# Car.net
KiCad netlist of a schematic drawn in EAGLE
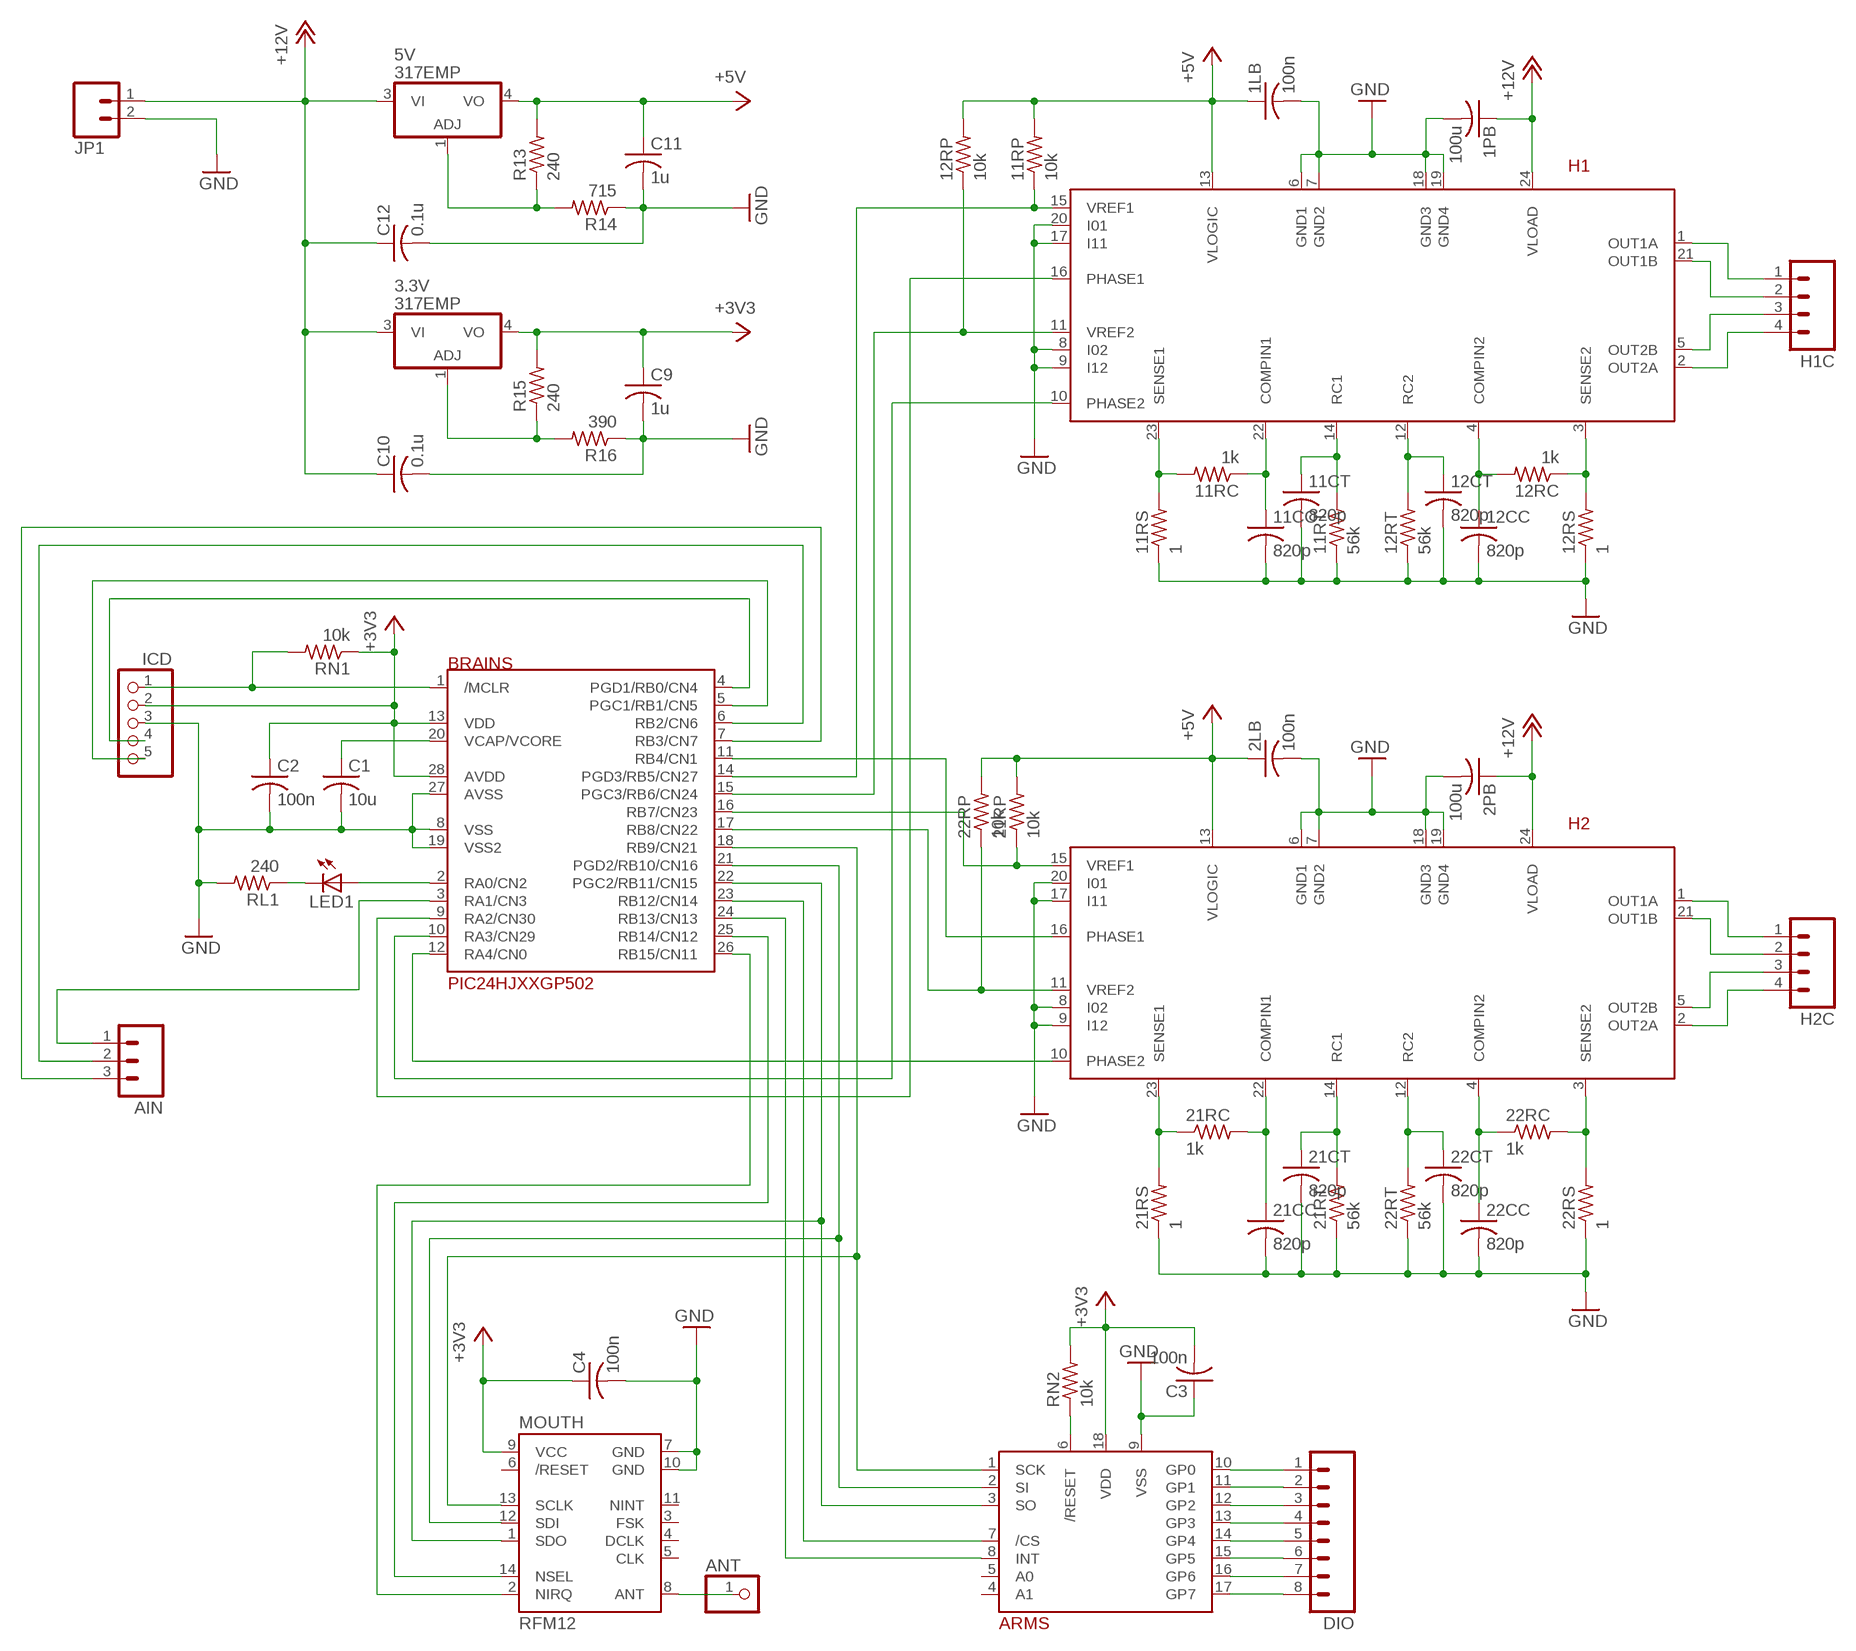
[diagram p0: schematic, sheet 1]

(export (version "E")
  (design (tool "Eeschema 10.0.6"))
  (components
    (comp (ref "1LB")
      (value "100n")
      (footprint "eagle-import:C0805")
      (libsource (lib "eagle-import") (part "C-USC0805"))
    )
    (comp (ref "1PB")
      (value "100u")
      (footprint "eagle-import:C0805")
      (libsource (lib "eagle-import") (part "C-USC0805"))
    )
    (comp (ref "2LB")
      (value "100n")
      (footprint "eagle-import:C0805")
      (libsource (lib "eagle-import") (part "C-USC0805"))
    )
    (comp (ref "2PB")
      (value "100u")
      (footprint "eagle-import:C0805")
      (libsource (lib "eagle-import") (part "C-USC0805"))
    )
    (comp (ref "3.3V")
      (value "317EMP")
      (footprint "eagle-import:SOT223")
      (libsource (lib "eagle-import") (part "317EMP"))
    )
    (comp (ref "5V")
      (value "317EMP")
      (footprint "eagle-import:SOT223")
      (libsource (lib "eagle-import") (part "317EMP"))
    )
    (comp (ref "11CC")
      (value "820p")
      (footprint "eagle-import:C0805")
      (libsource (lib "eagle-import") (part "C-USC0805"))
    )
    (comp (ref "11CT")
      (value "820p")
      (footprint "eagle-import:C0805")
      (libsource (lib "eagle-import") (part "C-USC0805"))
    )
    (comp (ref "11RC")
      (value "1k")
      (footprint "eagle-import:R0805")
      (libsource (lib "eagle-import") (part "R-US_R0805"))
    )
    (comp (ref "11RP")
      (value "10k")
      (footprint "eagle-import:R0805")
      (libsource (lib "eagle-import") (part "R-US_R0805"))
    )
    (comp (ref "11RS")
      (value "1")
      (footprint "eagle-import:R2512")
      (libsource (lib "eagle-import") (part "resistor_R-US_R2512"))
    )
    (comp (ref "11RT")
      (value "56k")
      (footprint "eagle-import:R0805")
      (libsource (lib "eagle-import") (part "R-US_R0805"))
    )
    (comp (ref "12CC")
      (value "820p")
      (footprint "eagle-import:C0805")
      (libsource (lib "eagle-import") (part "C-USC0805"))
    )
    (comp (ref "12CT")
      (value "820p")
      (footprint "eagle-import:C0805")
      (libsource (lib "eagle-import") (part "C-USC0805"))
    )
    (comp (ref "12RC")
      (value "1k")
      (footprint "eagle-import:R0805")
      (libsource (lib "eagle-import") (part "R-US_R0805"))
    )
    (comp (ref "12RP")
      (value "10k")
      (footprint "eagle-import:R0805")
      (libsource (lib "eagle-import") (part "R-US_R0805"))
    )
    (comp (ref "12RS")
      (value "1")
      (footprint "eagle-import:R2512")
      (libsource (lib "eagle-import") (part "resistor_R-US_R2512"))
    )
    (comp (ref "12RT")
      (value "56k")
      (footprint "eagle-import:R0805")
      (libsource (lib "eagle-import") (part "R-US_R0805"))
    )
    (comp (ref "21CC")
      (value "820p")
      (footprint "eagle-import:C0805")
      (libsource (lib "eagle-import") (part "C-USC0805"))
    )
    (comp (ref "21CT")
      (value "820p")
      (footprint "eagle-import:C0805")
      (libsource (lib "eagle-import") (part "C-USC0805"))
    )
    (comp (ref "21RC")
      (value "1k")
      (footprint "eagle-import:R0805")
      (libsource (lib "eagle-import") (part "R-US_R0805"))
    )
    (comp (ref "21RP")
      (value "10k")
      (footprint "eagle-import:R0805")
      (libsource (lib "eagle-import") (part "R-US_R0805"))
    )
    (comp (ref "21RS")
      (value "1")
      (footprint "eagle-import:R2512")
      (libsource (lib "eagle-import") (part "resistor_R-US_R2512"))
    )
    (comp (ref "21RT")
      (value "56k")
      (footprint "eagle-import:R0805")
      (libsource (lib "eagle-import") (part "R-US_R0805"))
    )
    (comp (ref "22CC")
      (value "820p")
      (footprint "eagle-import:C0805")
      (libsource (lib "eagle-import") (part "C-USC0805"))
    )
    (comp (ref "22CT")
      (value "820p")
      (footprint "eagle-import:C0805")
      (libsource (lib "eagle-import") (part "C-USC0805"))
    )
    (comp (ref "22RC")
      (value "1k")
      (footprint "eagle-import:R0805")
      (libsource (lib "eagle-import") (part "R-US_R0805"))
    )
    (comp (ref "22RP")
      (value "10k")
      (footprint "eagle-import:R0805")
      (libsource (lib "eagle-import") (part "R-US_R0805"))
    )
    (comp (ref "22RS")
      (value "1")
      (footprint "eagle-import:R2512")
      (libsource (lib "eagle-import") (part "resistor_R-US_R2512"))
    )
    (comp (ref "22RT")
      (value "56k")
      (footprint "eagle-import:R0805")
      (libsource (lib "eagle-import") (part "R-US_R0805"))
    )
    (comp (ref "AIN")
      (value "M03POLAR")
      (footprint "eagle-import:MOLEX-1X3")
      (libsource (lib "eagle-import") (part "M03POLAR"))
    )
    (comp (ref "ANT")
      (value "PINHD-1X1")
      (footprint "eagle-import:1X01")
      (libsource (lib "eagle-import") (part "PINHD-1X1"))
    )
    (comp (ref "ARMS")
      (value "MCP23S08")
      (footprint "eagle-import:SO-18W")
      (libsource (lib "eagle-import") (part "MCP23S08"))
    )
    (comp (ref "BRAINS")
      (value "PIC24HJXXGP502")
      (footprint "eagle-import:SO28W")
      (libsource (lib "eagle-import") (part "PIC24HJXXGP502"))
    )
    (comp (ref "C1")
      (value "10u")
      (footprint "eagle-import:C0805")
      (libsource (lib "eagle-import") (part "C-USC0805"))
    )
    (comp (ref "C2")
      (value "100n")
      (footprint "eagle-import:C0805")
      (libsource (lib "eagle-import") (part "C-USC0805"))
    )
    (comp (ref "C3")
      (value "100n")
      (footprint "eagle-import:C0805")
      (libsource (lib "eagle-import") (part "C-USC0805"))
    )
    (comp (ref "C4")
      (value "100n")
      (footprint "eagle-import:C0805")
      (libsource (lib "eagle-import") (part "C-USC0805"))
    )
    (comp (ref "C9")
      (value "1u")
      (footprint "eagle-import:C0805")
      (libsource (lib "eagle-import") (part "C-USC0805"))
    )
    (comp (ref "C10")
      (value "0.1u")
      (footprint "eagle-import:C0805")
      (libsource (lib "eagle-import") (part "C-USC0805"))
    )
    (comp (ref "C11")
      (value "1u")
      (footprint "eagle-import:C0805")
      (libsource (lib "eagle-import") (part "C-USC0805"))
    )
    (comp (ref "C12")
      (value "0.1u")
      (footprint "eagle-import:C0805")
      (libsource (lib "eagle-import") (part "C-USC0805"))
    )
    (comp (ref "DIO")
      (value "M081X08")
      (footprint "eagle-import:1X08")
      (libsource (lib "eagle-import") (part "M081X08"))
    )
    (comp (ref "H1")
      (value "MTS62C19A")
      (footprint "eagle-import:SOP24L")
      (libsource (lib "eagle-import") (part "MTS62C19A"))
    )
    (comp (ref "H1C")
      (value "M04POLAR")
      (footprint "eagle-import:MOLEX-1X4")
      (libsource (lib "eagle-import") (part "M04POLAR"))
    )
    (comp (ref "H2")
      (value "MTS62C19A")
      (footprint "eagle-import:SOP24L")
      (libsource (lib "eagle-import") (part "MTS62C19A"))
    )
    (comp (ref "H2C")
      (value "M04POLAR")
      (footprint "eagle-import:MOLEX-1X4")
      (libsource (lib "eagle-import") (part "M04POLAR"))
    )
    (comp (ref "ICD")
      (value "PINHD-1X5")
      (footprint "eagle-import:1X05")
      (libsource (lib "eagle-import") (part "PINHD-1X5"))
    )
    (comp (ref "JP1")
      (value "M02POLAR")
      (footprint "eagle-import:MOLEX-1X2")
      (libsource (lib "eagle-import") (part "M02POLAR"))
    )
    (comp (ref "LED1")
      (value "LEDCHIP-LED0805")
      (footprint "eagle-import:CHIP-LED0805")
      (libsource (lib "eagle-import") (part "LEDCHIP-LED0805"))
    )
    (comp (ref "MOUTH")
      (value "RFM12")
      (footprint "eagle-import:RFM12-XXX-S2")
      (libsource (lib "eagle-import") (part "RFM12"))
    )
    (comp (ref "R13")
      (value "240")
      (footprint "eagle-import:R0805")
      (libsource (lib "eagle-import") (part "R-US_R0805"))
    )
    (comp (ref "R14")
      (value "715")
      (footprint "eagle-import:R0805")
      (libsource (lib "eagle-import") (part "R-US_R0805"))
    )
    (comp (ref "R15")
      (value "240")
      (footprint "eagle-import:R0805")
      (libsource (lib "eagle-import") (part "R-US_R0805"))
    )
    (comp (ref "R16")
      (value "390")
      (footprint "eagle-import:R0805")
      (libsource (lib "eagle-import") (part "R-US_R0805"))
    )
    (comp (ref "RL1")
      (value "240")
      (footprint "eagle-import:R0805")
      (libsource (lib "eagle-import") (part "R-US_R0805"))
    )
    (comp (ref "RN1")
      (value "10k")
      (footprint "eagle-import:R0805")
      (libsource (lib "eagle-import") (part "R-US_R0805"))
    )
    (comp (ref "RN2")
      (value "10k")
      (footprint "eagle-import:R0805")
      (libsource (lib "eagle-import") (part "R-US_R0805"))
    )
  )
  (nets
    (net (code "1") (name "+3V3") (class "Default")
      (node (ref "3.3V") (pin "4") (pinfunction "VO_4") (pintype "passive"))
      (node (ref "ARMS") (pin "18") (pinfunction "VDD_18") (pintype "bidirectional"))
      (node (ref "BRAINS") (pin "13") (pinfunction "VDD_13") (pintype "bidirectional"))
      (node (ref "BRAINS") (pin "28") (pinfunction "AVDD_28") (pintype "bidirectional"))
      (node (ref "C2") (pin "1") (pinfunction "1_1") (pintype "passive"))
      (node (ref "C3") (pin "2") (pinfunction "2_2") (pintype "passive"))
      (node (ref "C4") (pin "1") (pinfunction "1_1") (pintype "passive"))
      (node (ref "C9") (pin "1") (pinfunction "1_1") (pintype "passive"))
      (node (ref "ICD") (pin "2") (pinfunction "2_2") (pintype "passive"))
      (node (ref "MOUTH") (pin "9") (pinfunction "VCC_9") (pintype "bidirectional"))
      (node (ref "R15") (pin "2") (pinfunction "2_2") (pintype "passive"))
      (node (ref "RN1") (pin "1") (pinfunction "1_1") (pintype "passive"))
      (node (ref "RN2") (pin "2") (pinfunction "2_2") (pintype "passive"))
    )
    (net (code "2") (name "+5V") (class "Default")
      (node (ref "11RP") (pin "2") (pinfunction "2_2") (pintype "passive"))
      (node (ref "12RP") (pin "2") (pinfunction "2_2") (pintype "passive"))
      (node (ref "1LB") (pin "1") (pinfunction "1_1") (pintype "passive"))
      (node (ref "21RP") (pin "2") (pinfunction "2_2") (pintype "passive"))
      (node (ref "22RP") (pin "2") (pinfunction "2_2") (pintype "passive"))
      (node (ref "2LB") (pin "1") (pinfunction "1_1") (pintype "passive"))
      (node (ref "5V") (pin "4") (pinfunction "VO_4") (pintype "passive"))
      (node (ref "C11") (pin "1") (pinfunction "1_1") (pintype "passive"))
      (node (ref "H1") (pin "13") (pinfunction "VLOGIC_13") (pintype "bidirectional"))
      (node (ref "H2") (pin "13") (pinfunction "VLOGIC_13") (pintype "bidirectional"))
      (node (ref "R13") (pin "2") (pinfunction "2_2") (pintype "passive"))
    )
    (net (code "3") (name "+12V") (class "Default")
      (node (ref "1PB") (pin "1") (pinfunction "1_1") (pintype "passive"))
      (node (ref "2PB") (pin "1") (pinfunction "1_1") (pintype "passive"))
      (node (ref "3.3V") (pin "3") (pinfunction "VI_3") (pintype "input"))
      (node (ref "5V") (pin "3") (pinfunction "VI_3") (pintype "input"))
      (node (ref "C10") (pin "1") (pinfunction "1_1") (pintype "passive"))
      (node (ref "C12") (pin "1") (pinfunction "1_1") (pintype "passive"))
      (node (ref "H1") (pin "24") (pinfunction "VLOAD_24") (pintype "bidirectional"))
      (node (ref "H2") (pin "24") (pinfunction "VLOAD_24") (pintype "bidirectional"))
      (node (ref "JP1") (pin "1") (pinfunction "1_1") (pintype "passive"))
    )
    (net (code "4") (name "GND") (class "Default")
      (node (ref "11CC") (pin "2") (pinfunction "2_2") (pintype "passive"))
      (node (ref "11CT") (pin "2") (pinfunction "2_2") (pintype "passive"))
      (node (ref "11RS") (pin "1") (pinfunction "1_1") (pintype "passive"))
      (node (ref "11RT") (pin "1") (pinfunction "1_1") (pintype "passive"))
      (node (ref "12CC") (pin "2") (pinfunction "2_2") (pintype "passive"))
      (node (ref "12CT") (pin "2") (pinfunction "2_2") (pintype "passive"))
      (node (ref "12RS") (pin "1") (pinfunction "1_1") (pintype "passive"))
      (node (ref "12RT") (pin "1") (pinfunction "1_1") (pintype "passive"))
      (node (ref "1LB") (pin "2") (pinfunction "2_2") (pintype "passive"))
      (node (ref "1PB") (pin "2") (pinfunction "2_2") (pintype "passive"))
      (node (ref "21CC") (pin "2") (pinfunction "2_2") (pintype "passive"))
      (node (ref "21CT") (pin "2") (pinfunction "2_2") (pintype "passive"))
      (node (ref "21RS") (pin "1") (pinfunction "1_1") (pintype "passive"))
      (node (ref "21RT") (pin "1") (pinfunction "1_1") (pintype "passive"))
      (node (ref "22CC") (pin "2") (pinfunction "2_2") (pintype "passive"))
      (node (ref "22CT") (pin "2") (pinfunction "2_2") (pintype "passive"))
      (node (ref "22RS") (pin "1") (pinfunction "1_1") (pintype "passive"))
      (node (ref "22RT") (pin "1") (pinfunction "1_1") (pintype "passive"))
      (node (ref "2LB") (pin "2") (pinfunction "2_2") (pintype "passive"))
      (node (ref "2PB") (pin "2") (pinfunction "2_2") (pintype "passive"))
      (node (ref "ARMS") (pin "9") (pinfunction "VSS_9") (pintype "bidirectional"))
      (node (ref "BRAINS") (pin "19") (pinfunction "VSS2_19") (pintype "bidirectional"))
      (node (ref "BRAINS") (pin "27") (pinfunction "AVSS_27") (pintype "bidirectional"))
      (node (ref "BRAINS") (pin "8") (pinfunction "VSS_8") (pintype "bidirectional"))
      (node (ref "C1") (pin "2") (pinfunction "2_2") (pintype "passive"))
      (node (ref "C10") (pin "2") (pinfunction "2_2") (pintype "passive"))
      (node (ref "C11") (pin "2") (pinfunction "2_2") (pintype "passive"))
      (node (ref "C12") (pin "2") (pinfunction "2_2") (pintype "passive"))
      (node (ref "C2") (pin "2") (pinfunction "2_2") (pintype "passive"))
      (node (ref "C3") (pin "1") (pinfunction "1_1") (pintype "passive"))
      (node (ref "C4") (pin "2") (pinfunction "2_2") (pintype "passive"))
      (node (ref "C9") (pin "2") (pinfunction "2_2") (pintype "passive"))
      (node (ref "H1") (pin "17") (pinfunction "I11_17") (pintype "bidirectional"))
      (node (ref "H1") (pin "18") (pinfunction "GND3_18") (pintype "bidirectional"))
      (node (ref "H1") (pin "19") (pinfunction "GND4_19") (pintype "bidirectional"))
      (node (ref "H1") (pin "20") (pinfunction "I01_20") (pintype "bidirectional"))
      (node (ref "H1") (pin "6") (pinfunction "GND1_6") (pintype "bidirectional"))
      (node (ref "H1") (pin "7") (pinfunction "GND2_7") (pintype "bidirectional"))
      (node (ref "H1") (pin "8") (pinfunction "I02_8") (pintype "bidirectional"))
      (node (ref "H1") (pin "9") (pinfunction "I12_9") (pintype "bidirectional"))
      (node (ref "H2") (pin "17") (pinfunction "I11_17") (pintype "bidirectional"))
      (node (ref "H2") (pin "18") (pinfunction "GND3_18") (pintype "bidirectional"))
      (node (ref "H2") (pin "19") (pinfunction "GND4_19") (pintype "bidirectional"))
      (node (ref "H2") (pin "20") (pinfunction "I01_20") (pintype "bidirectional"))
      (node (ref "H2") (pin "6") (pinfunction "GND1_6") (pintype "bidirectional"))
      (node (ref "H2") (pin "7") (pinfunction "GND2_7") (pintype "bidirectional"))
      (node (ref "H2") (pin "8") (pinfunction "I02_8") (pintype "bidirectional"))
      (node (ref "H2") (pin "9") (pinfunction "I12_9") (pintype "bidirectional"))
      (node (ref "ICD") (pin "3") (pinfunction "3_3") (pintype "passive"))
      (node (ref "JP1") (pin "2") (pinfunction "2_2") (pintype "passive"))
      (node (ref "MOUTH") (pin "10") (pinfunction "GND_10") (pintype "bidirectional"))
      (node (ref "MOUTH") (pin "7") (pinfunction "GND_7") (pintype "bidirectional"))
      (node (ref "R14") (pin "1") (pinfunction "1_1") (pintype "passive"))
      (node (ref "R16") (pin "1") (pinfunction "1_1") (pintype "passive"))
      (node (ref "RL1") (pin "2") (pinfunction "2_2") (pintype "passive"))
    )
    (net (code "5") (name "Net-(3.3V-ADJ)") (class "Default")
      (node (ref "3.3V") (pin "1") (pinfunction "ADJ_1") (pintype "input"))
      (node (ref "R15") (pin "1") (pinfunction "1_1") (pintype "passive"))
      (node (ref "R16") (pin "2") (pinfunction "2_2") (pintype "passive"))
    )
    (net (code "6") (name "Net-(5V-ADJ)") (class "Default")
      (node (ref "5V") (pin "1") (pinfunction "ADJ_1") (pintype "input"))
      (node (ref "R13") (pin "1") (pinfunction "1_1") (pintype "passive"))
      (node (ref "R14") (pin "2") (pinfunction "2_2") (pintype "passive"))
    )
    (net (code "7") (name "Net-(ARMS-GP0)") (class "Default")
      (node (ref "ARMS") (pin "10") (pinfunction "GP0_10") (pintype "bidirectional"))
      (node (ref "DIO") (pin "1") (pinfunction "1_1") (pintype "passive"))
    )
    (net (code "8") (name "Net-(ARMS-GP1)") (class "Default")
      (node (ref "ARMS") (pin "11") (pinfunction "GP1_11") (pintype "bidirectional"))
      (node (ref "DIO") (pin "2") (pinfunction "2_2") (pintype "passive"))
    )
    (net (code "9") (name "Net-(ARMS-GP2)") (class "Default")
      (node (ref "ARMS") (pin "12") (pinfunction "GP2_12") (pintype "bidirectional"))
      (node (ref "DIO") (pin "3") (pinfunction "3_3") (pintype "passive"))
    )
    (net (code "10") (name "Net-(ARMS-GP3)") (class "Default")
      (node (ref "ARMS") (pin "13") (pinfunction "GP3_13") (pintype "bidirectional"))
      (node (ref "DIO") (pin "4") (pinfunction "4_4") (pintype "passive"))
    )
    (net (code "11") (name "Net-(ARMS-GP4)") (class "Default")
      (node (ref "ARMS") (pin "14") (pinfunction "GP4_14") (pintype "bidirectional"))
      (node (ref "DIO") (pin "5") (pinfunction "5_5") (pintype "passive"))
    )
    (net (code "12") (name "Net-(ARMS-GP5)") (class "Default")
      (node (ref "ARMS") (pin "15") (pinfunction "GP5_15") (pintype "bidirectional"))
      (node (ref "DIO") (pin "6") (pinfunction "6_6") (pintype "passive"))
    )
    (net (code "13") (name "Net-(ARMS-GP6)") (class "Default")
      (node (ref "ARMS") (pin "16") (pinfunction "GP6_16") (pintype "bidirectional"))
      (node (ref "DIO") (pin "7") (pinfunction "7_7") (pintype "passive"))
    )
    (net (code "14") (name "Net-(ARMS-GP7)") (class "Default")
      (node (ref "ARMS") (pin "17") (pinfunction "GP7_17") (pintype "bidirectional"))
      (node (ref "DIO") (pin "8") (pinfunction "8_8") (pintype "passive"))
    )
    (net (code "15") (name "Net-(ARMS-INT)") (class "Default")
      (node (ref "ARMS") (pin "8") (pinfunction "INT_8") (pintype "bidirectional"))
      (node (ref "BRAINS") (pin "24") (pinfunction "RB13/CN13_24") (pintype "bidirectional"))
    )
    (net (code "16") (name "Net-(ARMS-SCK)") (class "Default")
      (node (ref "ARMS") (pin "1") (pinfunction "SCK_1") (pintype "bidirectional"))
      (node (ref "BRAINS") (pin "18") (pinfunction "RB9/CN21_18") (pintype "bidirectional"))
      (node (ref "MOUTH") (pin "13") (pinfunction "SCLK_13") (pintype "input"))
    )
    (net (code "17") (name "Net-(ARMS-SI)") (class "Default")
      (node (ref "ARMS") (pin "2") (pinfunction "SI_2") (pintype "bidirectional"))
      (node (ref "BRAINS") (pin "21") (pinfunction "PGD2/RB10/CN16_21") (pintype "bidirectional"))
      (node (ref "MOUTH") (pin "12") (pinfunction "SDI_12") (pintype "input"))
    )
    (net (code "18") (name "Net-(ARMS-SO)") (class "Default")
      (node (ref "ARMS") (pin "3") (pinfunction "SO_3") (pintype "bidirectional"))
      (node (ref "BRAINS") (pin "22") (pinfunction "PGC2/RB11/CN15_22") (pintype "bidirectional"))
      (node (ref "MOUTH") (pin "1") (pinfunction "SDO_1") (pintype "output"))
    )
    (net (code "19") (name "Net-(ARMS-{slash}CS)") (class "Default")
      (node (ref "ARMS") (pin "7") (pinfunction "/CS_7") (pintype "bidirectional"))
      (node (ref "BRAINS") (pin "23") (pinfunction "RB12/CN14_23") (pintype "bidirectional"))
    )
    (net (code "20") (name "Net-(ARMS-{slash}RESET)") (class "Default")
      (node (ref "ARMS") (pin "6") (pinfunction "/RESET_6") (pintype "bidirectional"))
      (node (ref "RN2") (pin "1") (pinfunction "1_1") (pintype "passive"))
    )
    (net (code "21") (name "Net-(BRAINS-PGC1{slash}RB1{slash}CN5)") (class "Default")
      (node (ref "BRAINS") (pin "5") (pinfunction "PGC1/RB1/CN5_5") (pintype "bidirectional"))
      (node (ref "ICD") (pin "5") (pinfunction "5_5") (pintype "passive"))
    )
    (net (code "22") (name "Net-(BRAINS-PGC3{slash}RB6{slash}CN24)") (class "Default")
      (node (ref "12RP") (pin "1") (pinfunction "1_1") (pintype "passive"))
      (node (ref "BRAINS") (pin "15") (pinfunction "PGC3/RB6/CN24_15") (pintype "bidirectional"))
      (node (ref "H1") (pin "11") (pinfunction "VREF2_11") (pintype "bidirectional"))
    )
    (net (code "23") (name "Net-(BRAINS-PGD1{slash}RB0{slash}CN4)") (class "Default")
      (node (ref "BRAINS") (pin "4") (pinfunction "PGD1/RB0/CN4_4") (pintype "bidirectional"))
      (node (ref "ICD") (pin "4") (pinfunction "4_4") (pintype "passive"))
    )
    (net (code "24") (name "Net-(BRAINS-PGD3{slash}RB5{slash}CN27)") (class "Default")
      (node (ref "11RP") (pin "1") (pinfunction "1_1") (pintype "passive"))
      (node (ref "BRAINS") (pin "14") (pinfunction "PGD3/RB5/CN27_14") (pintype "bidirectional"))
      (node (ref "H1") (pin "15") (pinfunction "VREF1_15") (pintype "bidirectional"))
    )
    (net (code "25") (name "Net-(BRAINS-RA0{slash}CN2)") (class "Default")
      (node (ref "BRAINS") (pin "2") (pinfunction "RA0/CN2_2") (pintype "bidirectional"))
      (node (ref "LED1") (pin "A") (pinfunction "A_A") (pintype "passive"))
    )
    (net (code "26") (name "Net-(BRAINS-RA1{slash}CN3)") (class "Default")
      (node (ref "AIN") (pin "1") (pinfunction "1_1") (pintype "passive"))
      (node (ref "BRAINS") (pin "3") (pinfunction "RA1/CN3_3") (pintype "bidirectional"))
    )
    (net (code "27") (name "Net-(BRAINS-RA2{slash}CN30)") (class "Default")
      (node (ref "BRAINS") (pin "9") (pinfunction "RA2/CN30_9") (pintype "bidirectional"))
      (node (ref "H1") (pin "16") (pinfunction "PHASE1_16") (pintype "bidirectional"))
    )
    (net (code "28") (name "Net-(BRAINS-RA3{slash}CN29)") (class "Default")
      (node (ref "BRAINS") (pin "10") (pinfunction "RA3/CN29_10") (pintype "bidirectional"))
      (node (ref "H1") (pin "10") (pinfunction "PHASE2_10") (pintype "bidirectional"))
    )
    (net (code "29") (name "Net-(BRAINS-RA4{slash}CN0)") (class "Default")
      (node (ref "BRAINS") (pin "12") (pinfunction "RA4/CN0_12") (pintype "bidirectional"))
      (node (ref "H2") (pin "10") (pinfunction "PHASE2_10") (pintype "bidirectional"))
    )
    (net (code "30") (name "Net-(BRAINS-RB2{slash}CN6)") (class "Default")
      (node (ref "AIN") (pin "2") (pinfunction "2_2") (pintype "passive"))
      (node (ref "BRAINS") (pin "6") (pinfunction "RB2/CN6_6") (pintype "bidirectional"))
    )
    (net (code "31") (name "Net-(BRAINS-RB3{slash}CN7)") (class "Default")
      (node (ref "AIN") (pin "3") (pinfunction "3_3") (pintype "passive"))
      (node (ref "BRAINS") (pin "7") (pinfunction "RB3/CN7_7") (pintype "bidirectional"))
    )
    (net (code "32") (name "Net-(BRAINS-RB4{slash}CN1)") (class "Default")
      (node (ref "BRAINS") (pin "11") (pinfunction "RB4/CN1_11") (pintype "bidirectional"))
      (node (ref "H2") (pin "16") (pinfunction "PHASE1_16") (pintype "bidirectional"))
    )
    (net (code "33") (name "Net-(BRAINS-RB7{slash}CN23)") (class "Default")
      (node (ref "21RP") (pin "1") (pinfunction "1_1") (pintype "passive"))
      (node (ref "BRAINS") (pin "16") (pinfunction "RB7/CN23_16") (pintype "bidirectional"))
      (node (ref "H2") (pin "15") (pinfunction "VREF1_15") (pintype "bidirectional"))
    )
    (net (code "34") (name "Net-(BRAINS-RB8{slash}CN22)") (class "Default")
      (node (ref "22RP") (pin "1") (pinfunction "1_1") (pintype "passive"))
      (node (ref "BRAINS") (pin "17") (pinfunction "RB8/CN22_17") (pintype "bidirectional"))
      (node (ref "H2") (pin "11") (pinfunction "VREF2_11") (pintype "bidirectional"))
    )
    (net (code "35") (name "Net-(BRAINS-RB14{slash}CN12)") (class "Default")
      (node (ref "BRAINS") (pin "25") (pinfunction "RB14/CN12_25") (pintype "bidirectional"))
      (node (ref "MOUTH") (pin "14") (pinfunction "NSEL_14") (pintype "input"))
    )
    (net (code "36") (name "Net-(BRAINS-RB15{slash}CN11)") (class "Default")
      (node (ref "BRAINS") (pin "26") (pinfunction "RB15/CN11_26") (pintype "bidirectional"))
      (node (ref "MOUTH") (pin "2") (pinfunction "NIRQ_2") (pintype "output"))
    )
    (net (code "37") (name "Net-(BRAINS-VCAP{slash}VCORE)") (class "Default")
      (node (ref "BRAINS") (pin "20") (pinfunction "VCAP/VCORE_20") (pintype "bidirectional"))
      (node (ref "C1") (pin "1") (pinfunction "1_1") (pintype "passive"))
    )
    (net (code "38") (name "Net-(BRAINS-{slash}MCLR)") (class "Default")
      (node (ref "BRAINS") (pin "1") (pinfunction "/MCLR_1") (pintype "bidirectional"))
      (node (ref "ICD") (pin "1") (pinfunction "1_1") (pintype "passive"))
      (node (ref "RN1") (pin "2") (pinfunction "2_2") (pintype "passive"))
    )
    (net (code "39") (name "Net-(H1-COMPIN1)") (class "Default")
      (node (ref "11CC") (pin "1") (pinfunction "1_1") (pintype "passive"))
      (node (ref "11RC") (pin "1") (pinfunction "1_1") (pintype "passive"))
      (node (ref "H1") (pin "22") (pinfunction "COMPIN1_22") (pintype "bidirectional"))
    )
    (net (code "40") (name "Net-(H1-COMPIN2)") (class "Default")
      (node (ref "12CC") (pin "1") (pinfunction "1_1") (pintype "passive"))
      (node (ref "12RC") (pin "2") (pinfunction "2_2") (pintype "passive"))
      (node (ref "H1") (pin "4") (pinfunction "COMPIN2_4") (pintype "bidirectional"))
    )
    (net (code "41") (name "Net-(H1-OUT1A)") (class "Default")
      (node (ref "H1") (pin "1") (pinfunction "OUT1A_1") (pintype "bidirectional"))
      (node (ref "H1C") (pin "1") (pinfunction "1_1") (pintype "passive"))
    )
    (net (code "42") (name "Net-(H1-OUT1B)") (class "Default")
      (node (ref "H1") (pin "21") (pinfunction "OUT1B_21") (pintype "bidirectional"))
      (node (ref "H1C") (pin "2") (pinfunction "2_2") (pintype "passive"))
    )
    (net (code "43") (name "Net-(H1-OUT2A)") (class "Default")
      (node (ref "H1") (pin "2") (pinfunction "OUT2A_2") (pintype "bidirectional"))
      (node (ref "H1C") (pin "4") (pinfunction "4_4") (pintype "passive"))
    )
    (net (code "44") (name "Net-(H1-OUT2B)") (class "Default")
      (node (ref "H1") (pin "5") (pinfunction "OUT2B_5") (pintype "bidirectional"))
      (node (ref "H1C") (pin "3") (pinfunction "3_3") (pintype "passive"))
    )
    (net (code "45") (name "Net-(H1-RC1)") (class "Default")
      (node (ref "11CT") (pin "1") (pinfunction "1_1") (pintype "passive"))
      (node (ref "11RT") (pin "2") (pinfunction "2_2") (pintype "passive"))
      (node (ref "H1") (pin "14") (pinfunction "RC1_14") (pintype "bidirectional"))
    )
    (net (code "46") (name "Net-(H1-RC2)") (class "Default")
      (node (ref "12CT") (pin "1") (pinfunction "1_1") (pintype "passive"))
      (node (ref "12RT") (pin "2") (pinfunction "2_2") (pintype "passive"))
      (node (ref "H1") (pin "12") (pinfunction "RC2_12") (pintype "bidirectional"))
    )
    (net (code "47") (name "Net-(H1-SENSE1)") (class "Default")
      (node (ref "11RC") (pin "2") (pinfunction "2_2") (pintype "passive"))
      (node (ref "11RS") (pin "2") (pinfunction "2_2") (pintype "passive"))
      (node (ref "H1") (pin "23") (pinfunction "SENSE1_23") (pintype "bidirectional"))
    )
    (net (code "48") (name "Net-(H1-SENSE2)") (class "Default")
      (node (ref "12RC") (pin "1") (pinfunction "1_1") (pintype "passive"))
      (node (ref "12RS") (pin "2") (pinfunction "2_2") (pintype "passive"))
      (node (ref "H1") (pin "3") (pinfunction "SENSE2_3") (pintype "bidirectional"))
    )
    (net (code "49") (name "Net-(H2-COMPIN1)") (class "Default")
      (node (ref "21CC") (pin "1") (pinfunction "1_1") (pintype "passive"))
      (node (ref "21RC") (pin "2") (pinfunction "2_2") (pintype "passive"))
      (node (ref "H2") (pin "22") (pinfunction "COMPIN1_22") (pintype "bidirectional"))
    )
    (net (code "50") (name "Net-(H2-COMPIN2)") (class "Default")
      (node (ref "22CC") (pin "1") (pinfunction "1_1") (pintype "passive"))
      (node (ref "22RC") (pin "1") (pinfunction "1_1") (pintype "passive"))
      (node (ref "H2") (pin "4") (pinfunction "COMPIN2_4") (pintype "bidirectional"))
    )
    (net (code "51") (name "Net-(H2-OUT1A)") (class "Default")
      (node (ref "H2") (pin "1") (pinfunction "OUT1A_1") (pintype "bidirectional"))
      (node (ref "H2C") (pin "1") (pinfunction "1_1") (pintype "passive"))
    )
    (net (code "52") (name "Net-(H2-OUT1B)") (class "Default")
      (node (ref "H2") (pin "21") (pinfunction "OUT1B_21") (pintype "bidirectional"))
      (node (ref "H2C") (pin "2") (pinfunction "2_2") (pintype "passive"))
    )
    (net (code "53") (name "Net-(H2-OUT2A)") (class "Default")
      (node (ref "H2") (pin "2") (pinfunction "OUT2A_2") (pintype "bidirectional"))
      (node (ref "H2C") (pin "4") (pinfunction "4_4") (pintype "passive"))
    )
    (net (code "54") (name "Net-(H2-OUT2B)") (class "Default")
      (node (ref "H2") (pin "5") (pinfunction "OUT2B_5") (pintype "bidirectional"))
      (node (ref "H2C") (pin "3") (pinfunction "3_3") (pintype "passive"))
    )
    (net (code "55") (name "Net-(H2-RC1)") (class "Default")
      (node (ref "21CT") (pin "1") (pinfunction "1_1") (pintype "passive"))
      (node (ref "21RT") (pin "2") (pinfunction "2_2") (pintype "passive"))
      (node (ref "H2") (pin "14") (pinfunction "RC1_14") (pintype "bidirectional"))
    )
    (net (code "56") (name "Net-(H2-RC2)") (class "Default")
      (node (ref "22CT") (pin "1") (pinfunction "1_1") (pintype "passive"))
      (node (ref "22RT") (pin "2") (pinfunction "2_2") (pintype "passive"))
      (node (ref "H2") (pin "12") (pinfunction "RC2_12") (pintype "bidirectional"))
    )
    (net (code "57") (name "Net-(H2-SENSE1)") (class "Default")
      (node (ref "21RC") (pin "1") (pinfunction "1_1") (pintype "passive"))
      (node (ref "21RS") (pin "2") (pinfunction "2_2") (pintype "passive"))
      (node (ref "H2") (pin "23") (pinfunction "SENSE1_23") (pintype "bidirectional"))
    )
    (net (code "58") (name "Net-(H2-SENSE2)") (class "Default")
      (node (ref "22RC") (pin "2") (pinfunction "2_2") (pintype "passive"))
      (node (ref "22RS") (pin "2") (pinfunction "2_2") (pintype "passive"))
      (node (ref "H2") (pin "3") (pinfunction "SENSE2_3") (pintype "bidirectional"))
    )
    (net (code "59") (name "Net-(LED1-PadC)") (class "Default")
      (node (ref "LED1") (pin "C") (pinfunction "C_C") (pintype "passive"))
      (node (ref "RL1") (pin "1") (pinfunction "1_1") (pintype "passive"))
    )
    (net (code "60") (name "Net-(MOUTH-ANT)") (class "Default")
      (node (ref "ANT") (pin "1") (pinfunction "1_1") (pintype "passive"))
      (node (ref "MOUTH") (pin "8") (pinfunction "ANT_8") (pintype "bidirectional"))
    )
    (net (code "61") (name "unconnected-(ARMS-A0-Pad5)") (class "Default")
      (node (ref "ARMS") (pin "5") (pinfunction "A0_5") (pintype "bidirectional"))
    )
    (net (code "62") (name "unconnected-(ARMS-A1-Pad4)") (class "Default")
      (node (ref "ARMS") (pin "4") (pinfunction "A1_4") (pintype "bidirectional"))
    )
    (net (code "63") (name "unconnected-(MOUTH-CLK-Pad5)") (class "Default")
      (node (ref "MOUTH") (pin "5") (pinfunction "CLK_5") (pintype "bidirectional"))
    )
    (net (code "64") (name "unconnected-(MOUTH-DCLK-Pad4)") (class "Default")
      (node (ref "MOUTH") (pin "4") (pinfunction "DCLK_4") (pintype "bidirectional"))
    )
    (net (code "65") (name "unconnected-(MOUTH-FSK-Pad3)") (class "Default")
      (node (ref "MOUTH") (pin "3") (pinfunction "FSK_3") (pintype "bidirectional"))
    )
    (net (code "66") (name "unconnected-(MOUTH-NINT-Pad11)") (class "Default")
      (node (ref "MOUTH") (pin "11") (pinfunction "NINT_11") (pintype "bidirectional"))
    )
    (net (code "67") (name "unconnected-(MOUTH-{slash}RESET-Pad6)") (class "Default")
      (node (ref "MOUTH") (pin "6") (pinfunction "/RESET_6") (pintype "bidirectional"))
    )
  )
)
